# X_--_0909.net
KiCad netlist of a schematic drawn in EasyEDA Pro
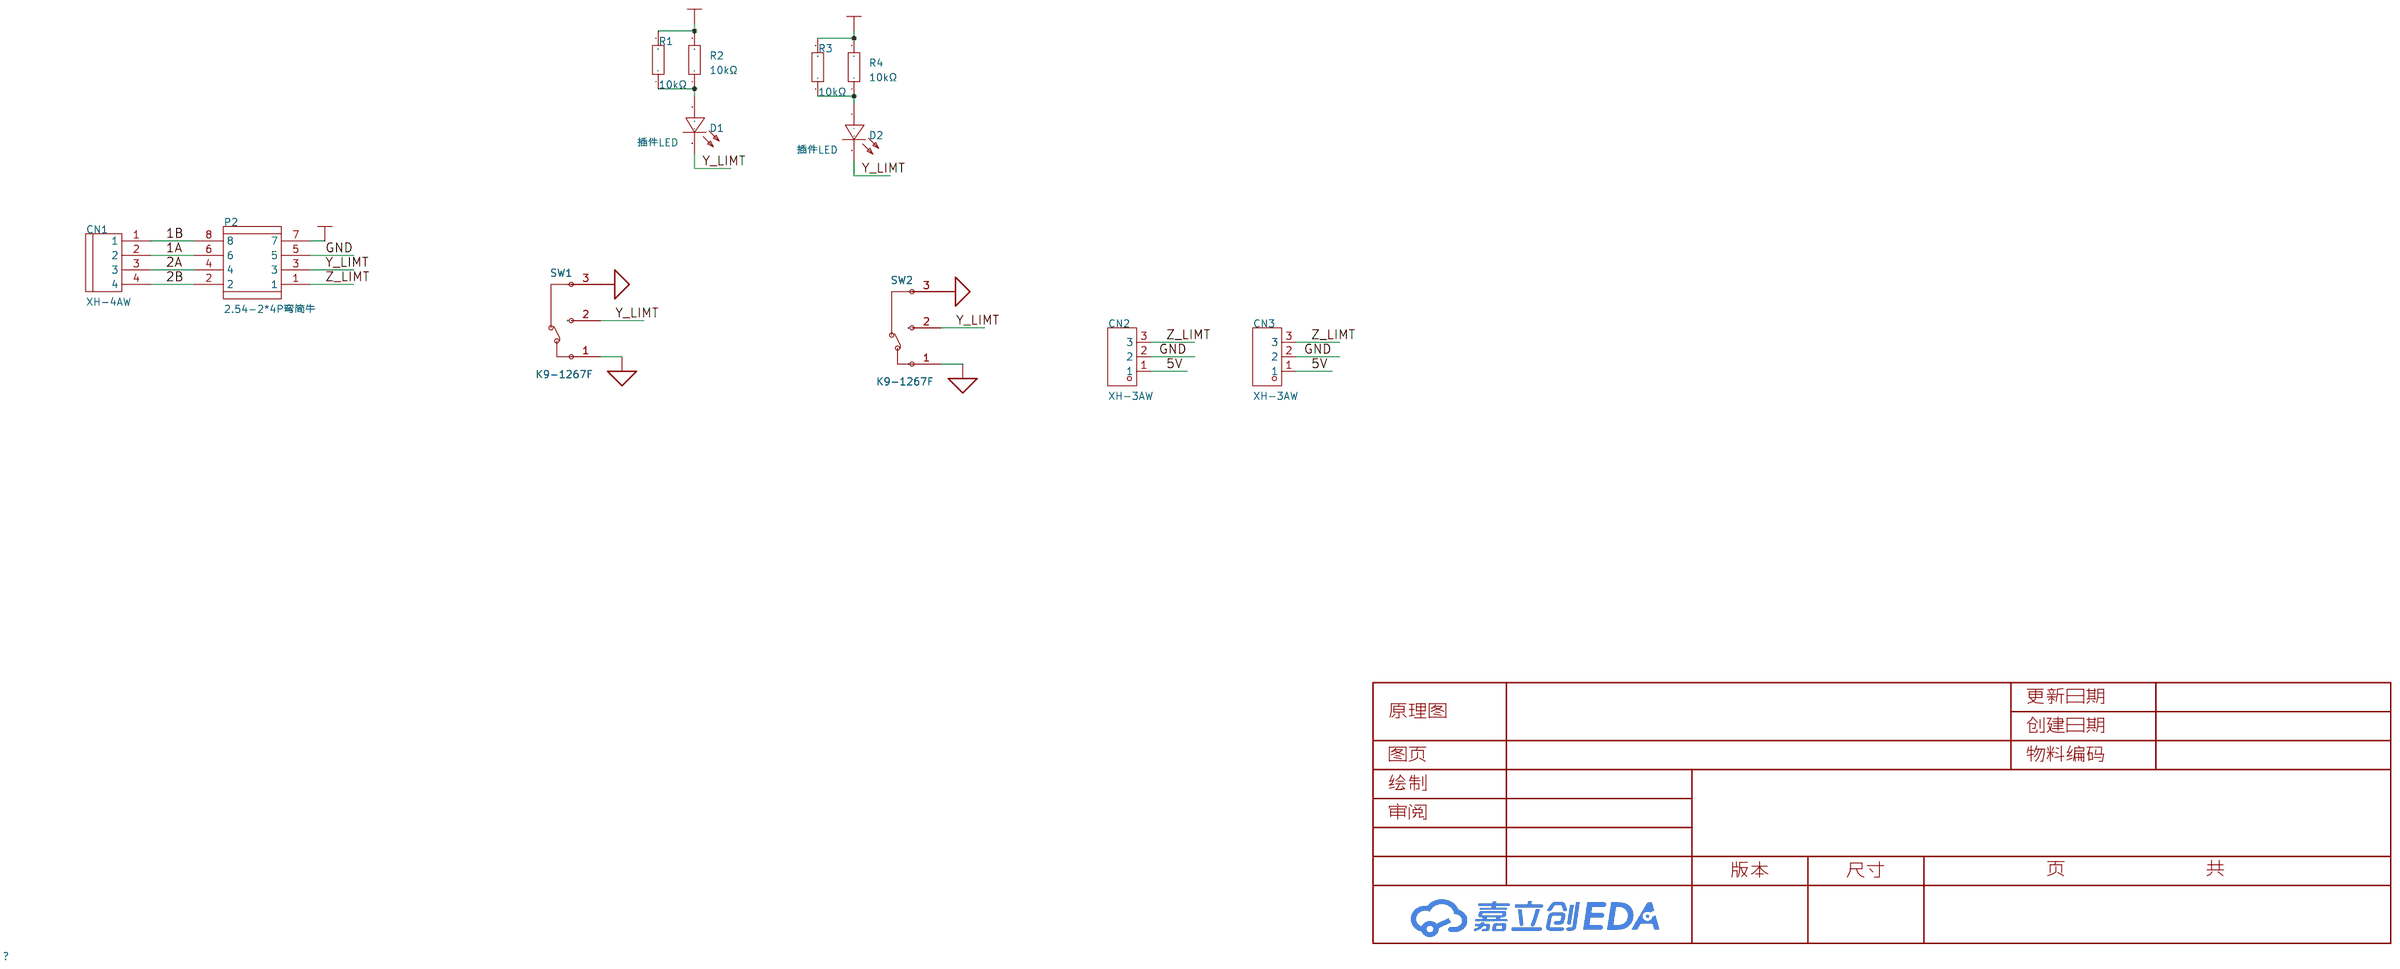
[diagram p0: schematic sheet]

(export (version "E")
  (design (tool "Eeschema 10.0.6"))
  (components
    (comp (ref "CN1")
      (value "XH-4AW")
      (footprint "easyedapro:CONN-TH_XH2.54-4AW")
      (description "参考系列:XH;间距:2.5mm;插针结构:1x4P;排数:1;每排PIN数:4;行距:-;安装方式:-;触头材质:磷青铜;")
      (fields (field (name "Manufacturer") "BOOMELE(博穆精密)"))
      (libsource (lib "easyedapro") (part "XH2.54-4AW"))
    )
    (comp (ref "CN2")
      (value "XH-3AW")
      (footprint "easyedapro:CONN-TH_3P-P2.50_XH-3A")
      (description "参考系列:XH;间距:2.5mm;插针结构:1x3P;排数:1;每排PIN数:3;行距:-;安装方式:-;触头材质:-;")
      (fields (field (name "Manufacturer") "BOOMELE(博穆精密)"))
      (libsource (lib "easyedapro") (part "XH-3AW_C18428"))
    )
    (comp (ref "CN3")
      (value "XH-3AW")
      (footprint "easyedapro:CONN-TH_3P-P2.50_XH-3A")
      (description "参考系列:XH;间距:2.5mm;插针结构:1x3P;排数:1;每排PIN数:3;行距:-;安装方式:-;触头材质:-;")
      (fields (field (name "Manufacturer") "BOOMELE(博穆精密)"))
      (libsource (lib "easyedapro") (part "XH-3AW_C18428"))
    )
    (comp (ref "D1")
      (value "插件LED")
      (footprint "easyedapro:LED-TH_BD3.8-P2.54-FD")
      (description "发光颜色:红灯;")
      (fields (field (name "Manufacturer") "EVERLIGHT(台湾亿光)"))
      (libsource (lib "easyedapro") (part "204-10SURC/S530-A3-L"))
    )
    (comp (ref "D2")
      (value "插件LED")
      (footprint "easyedapro:LED-TH_BD3.8-P2.54-FD")
      (description "发光颜色:红灯;")
      (fields (field (name "Manufacturer") "EVERLIGHT(台湾亿光)"))
      (libsource (lib "easyedapro") (part "204-10SURC/S530-A3-L"))
    )
    (comp (ref "P2")
      (value "2.54-2*4P弯简牛")
      (footprint "easyedapro:IDC-TH_8P-P2.54-H-R2-C4-S2.54")
      (description "连接器类型:简牛座;间距:2.54mm;结构:2x4P;封装形式:弯插;行距:2.54mm;排数:2;每排PIN数:4;触头材质:-;触头镀层:-;")
      (fields (field (name "Manufacturer") "BOOMELE(博穆精密)"))
      (libsource (lib "easyedapro") (part "IDC Box 2X4 2.54MM"))
    )
    (comp (ref "R1")
      (value "10kΩ")
      (footprint "easyedapro:R1206")
      (fields (field (name "Manufacturer Part") "RC1206FR-073KL") (field (name "Manufacturer") "YAGEO(国巨)"))
      (libsource (lib "easyedapro") (part "RC1206FR-073KL"))
    )
    (comp (ref "R2")
      (value "10kΩ")
      (footprint "easyedapro:R1206")
      (fields (field (name "Manufacturer Part") "RC1206FR-073KL") (field (name "Manufacturer") "YAGEO(国巨)"))
      (libsource (lib "easyedapro") (part "RC1206FR-073KL"))
    )
    (comp (ref "R3")
      (value "10kΩ")
      (footprint "easyedapro:R1206")
      (fields (field (name "Manufacturer Part") "RC1206FR-073KL") (field (name "Manufacturer") "YAGEO(国巨)"))
      (libsource (lib "easyedapro") (part "RC1206FR-073KL"))
    )
    (comp (ref "R4")
      (value "10kΩ")
      (footprint "easyedapro:R1206")
      (fields (field (name "Manufacturer Part") "RC1206FR-073KL") (field (name "Manufacturer") "YAGEO(国巨)"))
      (libsource (lib "easyedapro") (part "RC1206FR-073KL"))
    )
    (comp (ref "SW1")
      (value "K9-1267F")
      (footprint "easyedapro:SW-TH_K9-1267F")
      (fields (field (name "Manufacturer") "韩国韩荣"))
      (libsource (lib "easyedapro") (part "K9-1267F"))
    )
    (comp (ref "SW2")
      (value "K9-1267F")
      (footprint "easyedapro:SW-TH_K9-1267F")
      (fields (field (name "Manufacturer") "韩国韩荣"))
      (libsource (lib "easyedapro") (part "K9-1267F"))
    )
  )
  (nets
    (net (code "1") (name "/1A") (class "Default")
      (node (ref "CN1") (pin "2") (pinfunction "2_2") (pintype "input"))
      (node (ref "P2") (pin "6") (pinfunction "6_6") (pintype "unspecified"))
    )
    (net (code "2") (name "/1B") (class "Default")
      (node (ref "CN1") (pin "1") (pinfunction "1_1") (pintype "input"))
      (node (ref "P2") (pin "8") (pinfunction "8_8") (pintype "unspecified"))
    )
    (net (code "3") (name "/2A") (class "Default")
      (node (ref "CN1") (pin "3") (pinfunction "3_3") (pintype "input"))
      (node (ref "P2") (pin "4") (pinfunction "4_4") (pintype "unspecified"))
    )
    (net (code "4") (name "/2B") (class "Default")
      (node (ref "CN1") (pin "4") (pinfunction "4_4") (pintype "input"))
      (node (ref "P2") (pin "2") (pinfunction "2_2") (pintype "unspecified"))
    )
    (net (code "5") (name "/Y_LIMT") (class "Default")
      (node (ref "D1") (pin "2") (pinfunction "K_2") (pintype "input"))
      (node (ref "D2") (pin "2") (pinfunction "K_2") (pintype "input"))
      (node (ref "P2") (pin "3") (pinfunction "3_3") (pintype "unspecified"))
      (node (ref "SW1") (pin "2") (pinfunction "NO_2") (pintype "input"))
      (node (ref "SW2") (pin "2") (pinfunction "NO_2") (pintype "input"))
    )
    (net (code "6") (name "/Z_LIMT") (class "Default")
      (node (ref "CN2") (pin "3") (pinfunction "3_3") (pintype "input"))
      (node (ref "CN3") (pin "3") (pinfunction "3_3") (pintype "input"))
      (node (ref "P2") (pin "1") (pinfunction "1_1") (pintype "unspecified"))
    )
    (net (code "7") (name "5V") (class "Default")
      (node (ref "CN2") (pin "1") (pinfunction "1_1") (pintype "input"))
      (node (ref "CN3") (pin "1") (pinfunction "1_1") (pintype "input"))
      (node (ref "P2") (pin "7") (pinfunction "7_7") (pintype "unspecified"))
      (node (ref "R1") (pin "2") (pinfunction "2_2") (pintype "input"))
      (node (ref "R2") (pin "2") (pinfunction "2_2") (pintype "input"))
      (node (ref "R3") (pin "2") (pinfunction "2_2") (pintype "input"))
      (node (ref "R4") (pin "2") (pinfunction "2_2") (pintype "input"))
    )
    (net (code "8") (name "GND") (class "Default")
      (node (ref "CN2") (pin "2") (pinfunction "2_2") (pintype "input"))
      (node (ref "CN3") (pin "2") (pinfunction "2_2") (pintype "input"))
      (node (ref "P2") (pin "5") (pinfunction "5_5") (pintype "unspecified"))
      (node (ref "SW1") (pin "1") (pinfunction "C_1") (pintype "input"))
      (node (ref "SW1") (pin "3") (pinfunction "NC_3") (pintype "input"))
      (node (ref "SW2") (pin "1") (pinfunction "C_1") (pintype "input"))
      (node (ref "SW2") (pin "3") (pinfunction "NC_3") (pintype "input"))
    )
    (net (code "9") (name "Net-(D1-A)") (class "Default")
      (node (ref "D1") (pin "1") (pinfunction "A_1") (pintype "input"))
      (node (ref "R1") (pin "1") (pinfunction "1_1") (pintype "input"))
      (node (ref "R2") (pin "1") (pinfunction "1_1") (pintype "input"))
    )
    (net (code "10") (name "Net-(D2-A)") (class "Default")
      (node (ref "D2") (pin "1") (pinfunction "A_1") (pintype "input"))
      (node (ref "R3") (pin "1") (pinfunction "1_1") (pintype "input"))
      (node (ref "R4") (pin "1") (pinfunction "1_1") (pintype "input"))
    )
  )
)
